# mimic1705.net
KiCad netlist of a schematic drawn in EAGLE
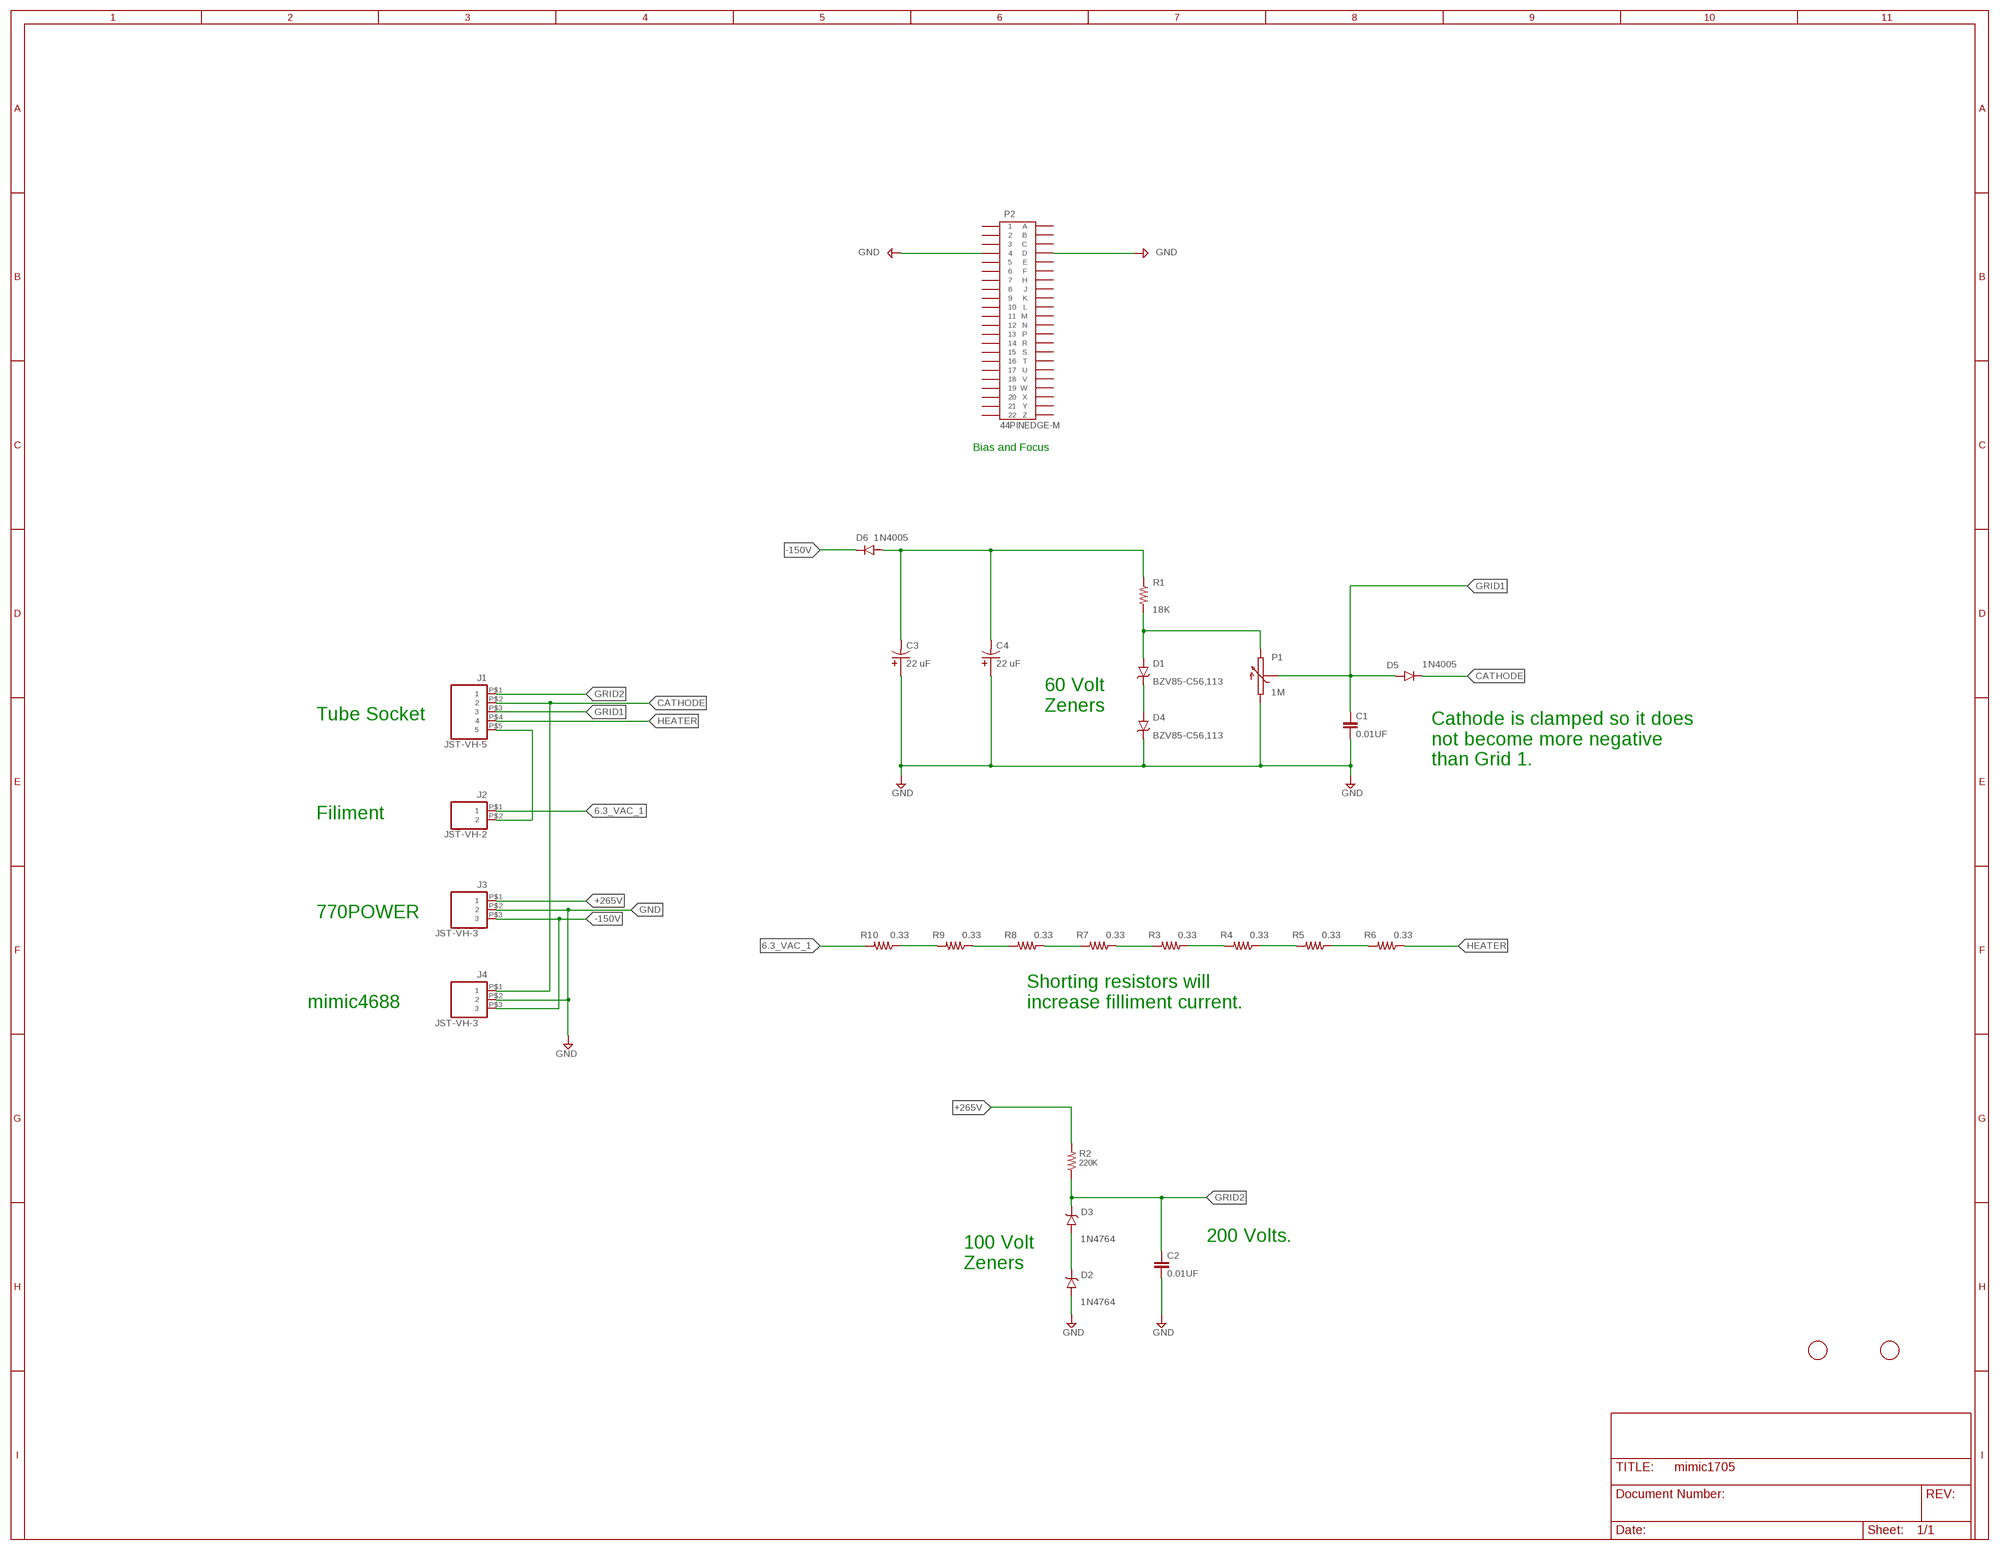
[diagram p0: schematic, sheet 1]

(export (version "E")
  (design (tool "Eeschema 10.0.6"))
  (components
    (comp (ref "C1")
      (value "0.01UF")
      (footprint "eagle-import:5MM_TH")
      (libsource (lib "eagle-import") (part "CAP_5MM"))
    )
    (comp (ref "C2")
      (value "0.01UF")
      (footprint "eagle-import:5MM_TH")
      (libsource (lib "eagle-import") (part "CAP_5MM"))
    )
    (comp (ref "C3")
      (value "22 uF")
      (footprint "eagle-import:AXIAL10X26")
      (libsource (lib "eagle-import") (part "CAP100UF200V"))
    )
    (comp (ref "C4")
      (value "22 uF")
      (footprint "eagle-import:AXIAL10X26")
      (libsource (lib "eagle-import") (part "CAP100UF200V"))
    )
    (comp (ref "D1")
      (value "BZV85-C56,113")
      (footprint "eagle-import:DO-41-10")
      (libsource (lib "eagle-import") (part "BZV85-C56,113"))
    )
    (comp (ref "D2")
      (value "1N4764")
      (footprint "eagle-import:DO-41-10")
      (libsource (lib "eagle-import") (part "1N4764A"))
    )
    (comp (ref "D3")
      (value "1N4764")
      (footprint "eagle-import:DO-41-10")
      (libsource (lib "eagle-import") (part "1N4764A"))
    )
    (comp (ref "D4")
      (value "BZV85-C56,113")
      (footprint "eagle-import:DO-41-10")
      (libsource (lib "eagle-import") (part "BZV85-C56,113"))
    )
    (comp (ref "D5")
      (value "1N4005")
      (footprint "eagle-import:DO-41-10")
      (libsource (lib "eagle-import") (part "1N400X"))
    )
    (comp (ref "D6")
      (value "1N4005")
      (footprint "eagle-import:DO-41-10")
      (libsource (lib "eagle-import") (part "1N400X"))
    )
    (comp (ref "J1")
      (value "JST-VH-5")
      (footprint "eagle-import:VHR-5N")
      (libsource (lib "eagle-import") (part "JST-VH-5"))
    )
    (comp (ref "J2")
      (value "JST-VH-2")
      (footprint "eagle-import:VHR-2N")
      (libsource (lib "eagle-import") (part "JST-VH-2"))
    )
    (comp (ref "J3")
      (value "JST-VH-3")
      (footprint "eagle-import:VHR-3N")
      (libsource (lib "eagle-import") (part "JST-VH-3"))
    )
    (comp (ref "J4")
      (value "JST-VH-3")
      (footprint "eagle-import:VHR-3N")
      (libsource (lib "eagle-import") (part "JST-VH-3"))
    )
    (comp (ref "P1")
      (value "1M")
      (footprint "eagle-import:3006P")
      (libsource (lib "eagle-import") (part "POT-3006P"))
    )
    (comp (ref "P2")
      (value "44PINEDGE-M")
      (footprint "eagle-import:44PINEDGE")
      (libsource (lib "eagle-import") (part "44PINEDGE-M"))
    )
    (comp (ref "R1")
      (value "18K")
      (footprint "eagle-import:0207_10")
      (libsource (lib "eagle-import") (part "RES-V"))
    )
    (comp (ref "R2")
      (value "220K")
      (footprint "eagle-import:0207_10")
      (libsource (lib "eagle-import") (part "RES-V"))
    )
    (comp (ref "R3")
      (value "0.33")
      (footprint "eagle-import:0309_12")
      (libsource (lib "eagle-import") (part "R-1/2WATT"))
    )
    (comp (ref "R4")
      (value "0.33")
      (footprint "eagle-import:0309_12")
      (libsource (lib "eagle-import") (part "R-1/2WATT"))
    )
    (comp (ref "R5")
      (value "0.33")
      (footprint "eagle-import:0309_12")
      (libsource (lib "eagle-import") (part "R-1/2WATT"))
    )
    (comp (ref "R6")
      (value "0.33")
      (footprint "eagle-import:0309_12")
      (libsource (lib "eagle-import") (part "R-1/2WATT"))
    )
    (comp (ref "R7")
      (value "0.33")
      (footprint "eagle-import:0309_12")
      (libsource (lib "eagle-import") (part "R-1/2WATT"))
    )
    (comp (ref "R8")
      (value "0.33")
      (footprint "eagle-import:0309_12")
      (libsource (lib "eagle-import") (part "R-1/2WATT"))
    )
    (comp (ref "R9")
      (value "0.33")
      (footprint "eagle-import:0309_12")
      (libsource (lib "eagle-import") (part "R-1/2WATT"))
    )
    (comp (ref "R10")
      (value "0.33")
      (footprint "eagle-import:0309_12")
      (libsource (lib "eagle-import") (part "R-1/2WATT"))
    )
    (comp (ref "U$1")
      (value "FIDUCIAL")
      (footprint "eagle-import:FIDUCIAL_1MM")
      (libsource (lib "eagle-import") (part "FIDUCIAL"))
    )
    (comp (ref "U$2")
      (value "FIDUCIAL")
      (footprint "eagle-import:FIDUCIAL_1MM")
      (libsource (lib "eagle-import") (part "FIDUCIAL"))
    )
  )
  (nets
    (net (code "1") (name "+265V") (class "Default")
      (node (ref "J3") (pin "P$1") (pinfunction "1_P$1") (pintype "bidirectional"))
      (node (ref "R2") (pin "2") (pinfunction "P$2_2") (pintype "passive"))
    )
    (net (code "2") (name "-150V") (class "Default")
      (node (ref "D6") (pin "C") (pinfunction "C_C") (pintype "passive"))
      (node (ref "J3") (pin "P$3") (pinfunction "3_P$3") (pintype "bidirectional"))
      (node (ref "J4") (pin "P$3") (pinfunction "3_P$3") (pintype "bidirectional"))
    )
    (net (code "3") (name "6.3_VAC_1") (class "Default")
      (node (ref "J2") (pin "P$1") (pinfunction "1_P$1") (pintype "bidirectional"))
      (node (ref "R10") (pin "2") (pinfunction "P$2_2") (pintype "passive"))
    )
    (net (code "4") (name "CATHODE") (class "Default")
      (node (ref "D5") (pin "C") (pinfunction "C_C") (pintype "passive"))
      (node (ref "J1") (pin "P$2") (pinfunction "2_P$2") (pintype "bidirectional"))
      (node (ref "J4") (pin "P$1") (pinfunction "1_P$1") (pintype "bidirectional"))
    )
    (net (code "5") (name "GND") (class "Default")
      (node (ref "C1") (pin "2") (pinfunction "2_2") (pintype "passive"))
      (node (ref "C2") (pin "2") (pinfunction "2_2") (pintype "passive"))
      (node (ref "C3") (pin "P$1") (pinfunction "1_P$1") (pintype "passive"))
      (node (ref "C4") (pin "P$1") (pinfunction "1_P$1") (pintype "passive"))
      (node (ref "D2") (pin "A") (pinfunction "A_A") (pintype "passive"))
      (node (ref "D4") (pin "C") (pinfunction "C_C") (pintype "passive"))
      (node (ref "J3") (pin "P$2") (pinfunction "2_P$2") (pintype "bidirectional"))
      (node (ref "J4") (pin "P$2") (pinfunction "2_P$2") (pintype "bidirectional"))
      (node (ref "P1") (pin "1") (pinfunction "1_1") (pintype "passive"))
      (node (ref "P2") (pin "4") (pinfunction "4_4") (pintype "passive"))
      (node (ref "P2") (pin "D") (pinfunction "D_D") (pintype "passive"))
    )
    (net (code "6") (name "GRID1") (class "Default")
      (node (ref "C1") (pin "1") (pinfunction "1_1") (pintype "passive"))
      (node (ref "D5") (pin "A") (pinfunction "A_A") (pintype "passive"))
      (node (ref "J1") (pin "P$3") (pinfunction "3_P$3") (pintype "bidirectional"))
      (node (ref "P1") (pin "2") (pinfunction "2_2") (pintype "passive"))
    )
    (net (code "7") (name "GRID2") (class "Default")
      (node (ref "C2") (pin "1") (pinfunction "1_1") (pintype "passive"))
      (node (ref "D3") (pin "C") (pinfunction "C_C") (pintype "passive"))
      (node (ref "J1") (pin "P$1") (pinfunction "1_P$1") (pintype "bidirectional"))
      (node (ref "R2") (pin "1") (pinfunction "P$1_1") (pintype "passive"))
    )
    (net (code "8") (name "HEATER") (class "Default")
      (node (ref "J1") (pin "P$4") (pinfunction "4_P$4") (pintype "bidirectional"))
      (node (ref "R6") (pin "1") (pinfunction "P$1_1") (pintype "passive"))
    )
    (net (code "9") (name "Net-(C3-2)") (class "Default")
      (node (ref "C3") (pin "P$2") (pinfunction "2_P$2") (pintype "passive"))
      (node (ref "C4") (pin "P$2") (pinfunction "2_P$2") (pintype "passive"))
      (node (ref "D6") (pin "A") (pinfunction "A_A") (pintype "passive"))
      (node (ref "R1") (pin "1") (pinfunction "P$1_1") (pintype "passive"))
    )
    (net (code "10") (name "Net-(D1-PadC)") (class "Default")
      (node (ref "D1") (pin "C") (pinfunction "C_C") (pintype "passive"))
      (node (ref "D4") (pin "A") (pinfunction "A_A") (pintype "passive"))
    )
    (net (code "11") (name "Net-(D2-PadC)") (class "Default")
      (node (ref "D2") (pin "C") (pinfunction "C_C") (pintype "passive"))
      (node (ref "D3") (pin "A") (pinfunction "A_A") (pintype "passive"))
    )
    (net (code "12") (name "Net-(J1-5)") (class "Default")
      (node (ref "J1") (pin "P$5") (pinfunction "5_P$5") (pintype "bidirectional"))
      (node (ref "J2") (pin "P$2") (pinfunction "2_P$2") (pintype "bidirectional"))
    )
    (net (code "13") (name "Net-(R1-P$2)") (class "Default")
      (node (ref "D1") (pin "A") (pinfunction "A_A") (pintype "passive"))
      (node (ref "P1") (pin "3") (pinfunction "3_3") (pintype "passive"))
      (node (ref "R1") (pin "2") (pinfunction "P$2_2") (pintype "passive"))
    )
    (net (code "14") (name "Net-(R3-P$1)") (class "Default")
      (node (ref "R3") (pin "1") (pinfunction "P$1_1") (pintype "passive"))
      (node (ref "R4") (pin "2") (pinfunction "P$2_2") (pintype "passive"))
    )
    (net (code "15") (name "Net-(R3-P$2)") (class "Default")
      (node (ref "R3") (pin "2") (pinfunction "P$2_2") (pintype "passive"))
      (node (ref "R7") (pin "1") (pinfunction "P$1_1") (pintype "passive"))
    )
    (net (code "16") (name "Net-(R4-P$1)") (class "Default")
      (node (ref "R4") (pin "1") (pinfunction "P$1_1") (pintype "passive"))
      (node (ref "R5") (pin "2") (pinfunction "P$2_2") (pintype "passive"))
    )
    (net (code "17") (name "Net-(R5-P$1)") (class "Default")
      (node (ref "R5") (pin "1") (pinfunction "P$1_1") (pintype "passive"))
      (node (ref "R6") (pin "2") (pinfunction "P$2_2") (pintype "passive"))
    )
    (net (code "18") (name "Net-(R7-P$2)") (class "Default")
      (node (ref "R7") (pin "2") (pinfunction "P$2_2") (pintype "passive"))
      (node (ref "R8") (pin "1") (pinfunction "P$1_1") (pintype "passive"))
    )
    (net (code "19") (name "Net-(R8-P$2)") (class "Default")
      (node (ref "R8") (pin "2") (pinfunction "P$2_2") (pintype "passive"))
      (node (ref "R9") (pin "1") (pinfunction "P$1_1") (pintype "passive"))
    )
    (net (code "20") (name "Net-(R10-P$1)") (class "Default")
      (node (ref "R10") (pin "1") (pinfunction "P$1_1") (pintype "passive"))
      (node (ref "R9") (pin "2") (pinfunction "P$2_2") (pintype "passive"))
    )
    (net (code "21") (name "unconnected-(P2-Pad1)") (class "Default")
      (node (ref "P2") (pin "1") (pinfunction "1_1") (pintype "passive"))
    )
    (net (code "22") (name "unconnected-(P2-Pad2)") (class "Default")
      (node (ref "P2") (pin "2") (pinfunction "2_2") (pintype "passive"))
    )
    (net (code "23") (name "unconnected-(P2-Pad3)") (class "Default")
      (node (ref "P2") (pin "3") (pinfunction "3_3") (pintype "passive"))
    )
    (net (code "24") (name "unconnected-(P2-Pad5)") (class "Default")
      (node (ref "P2") (pin "5") (pinfunction "5_5") (pintype "passive"))
    )
    (net (code "25") (name "unconnected-(P2-Pad6)") (class "Default")
      (node (ref "P2") (pin "6") (pinfunction "6_6") (pintype "passive"))
    )
    (net (code "26") (name "unconnected-(P2-Pad7)") (class "Default")
      (node (ref "P2") (pin "7") (pinfunction "7_7") (pintype "passive"))
    )
    (net (code "27") (name "unconnected-(P2-Pad8)") (class "Default")
      (node (ref "P2") (pin "8") (pinfunction "8_8") (pintype "passive"))
    )
    (net (code "28") (name "unconnected-(P2-Pad9)") (class "Default")
      (node (ref "P2") (pin "9") (pinfunction "9_9") (pintype "passive"))
    )
    (net (code "29") (name "unconnected-(P2-Pad10)") (class "Default")
      (node (ref "P2") (pin "10") (pinfunction "10_10") (pintype "passive"))
    )
    (net (code "30") (name "unconnected-(P2-Pad11)") (class "Default")
      (node (ref "P2") (pin "11") (pinfunction "11_11") (pintype "passive"))
    )
    (net (code "31") (name "unconnected-(P2-Pad12)") (class "Default")
      (node (ref "P2") (pin "12") (pinfunction "12_12") (pintype "passive"))
    )
    (net (code "32") (name "unconnected-(P2-Pad13)") (class "Default")
      (node (ref "P2") (pin "13") (pinfunction "13_13") (pintype "passive"))
    )
    (net (code "33") (name "unconnected-(P2-Pad14)") (class "Default")
      (node (ref "P2") (pin "14") (pinfunction "14_14") (pintype "passive"))
    )
    (net (code "34") (name "unconnected-(P2-Pad15)") (class "Default")
      (node (ref "P2") (pin "15") (pinfunction "15_15") (pintype "passive"))
    )
    (net (code "35") (name "unconnected-(P2-Pad16)") (class "Default")
      (node (ref "P2") (pin "16") (pinfunction "16_16") (pintype "passive"))
    )
    (net (code "36") (name "unconnected-(P2-Pad17)") (class "Default")
      (node (ref "P2") (pin "17") (pinfunction "17_17") (pintype "passive"))
    )
    (net (code "37") (name "unconnected-(P2-Pad18)") (class "Default")
      (node (ref "P2") (pin "18") (pinfunction "18_18") (pintype "passive"))
    )
    (net (code "38") (name "unconnected-(P2-Pad19)") (class "Default")
      (node (ref "P2") (pin "19") (pinfunction "19_19") (pintype "passive"))
    )
    (net (code "39") (name "unconnected-(P2-Pad20)") (class "Default")
      (node (ref "P2") (pin "20") (pinfunction "20_20") (pintype "passive"))
    )
    (net (code "40") (name "unconnected-(P2-Pad21)") (class "Default")
      (node (ref "P2") (pin "21") (pinfunction "21_21") (pintype "passive"))
    )
    (net (code "41") (name "unconnected-(P2-Pad22)") (class "Default")
      (node (ref "P2") (pin "22") (pinfunction "22_22") (pintype "passive"))
    )
    (net (code "42") (name "unconnected-(P2-PadA)") (class "Default")
      (node (ref "P2") (pin "A") (pinfunction "A_A") (pintype "passive"))
    )
    (net (code "43") (name "unconnected-(P2-PadB)") (class "Default")
      (node (ref "P2") (pin "B") (pinfunction "B_B") (pintype "passive"))
    )
    (net (code "44") (name "unconnected-(P2-PadC)") (class "Default")
      (node (ref "P2") (pin "C") (pinfunction "C_C") (pintype "passive"))
    )
    (net (code "45") (name "unconnected-(P2-PadE)") (class "Default")
      (node (ref "P2") (pin "E") (pinfunction "E_E") (pintype "passive"))
    )
    (net (code "46") (name "unconnected-(P2-PadF)") (class "Default")
      (node (ref "P2") (pin "F") (pinfunction "F_F") (pintype "passive"))
    )
    (net (code "47") (name "unconnected-(P2-PadH)") (class "Default")
      (node (ref "P2") (pin "H") (pinfunction "H_H") (pintype "passive"))
    )
    (net (code "48") (name "unconnected-(P2-PadJ)") (class "Default")
      (node (ref "P2") (pin "J") (pinfunction "J_J") (pintype "passive"))
    )
    (net (code "49") (name "unconnected-(P2-PadK)") (class "Default")
      (node (ref "P2") (pin "K") (pinfunction "K_K") (pintype "passive"))
    )
    (net (code "50") (name "unconnected-(P2-PadL)") (class "Default")
      (node (ref "P2") (pin "L") (pinfunction "L_L") (pintype "passive"))
    )
    (net (code "51") (name "unconnected-(P2-PadM)") (class "Default")
      (node (ref "P2") (pin "M") (pinfunction "M_M") (pintype "passive"))
    )
    (net (code "52") (name "unconnected-(P2-PadN)") (class "Default")
      (node (ref "P2") (pin "N") (pinfunction "N_N") (pintype "passive"))
    )
    (net (code "53") (name "unconnected-(P2-PadP)") (class "Default")
      (node (ref "P2") (pin "P") (pinfunction "P_P") (pintype "passive"))
    )
    (net (code "54") (name "unconnected-(P2-PadR)") (class "Default")
      (node (ref "P2") (pin "R") (pinfunction "R_R") (pintype "passive"))
    )
    (net (code "55") (name "unconnected-(P2-PadS)") (class "Default")
      (node (ref "P2") (pin "S") (pinfunction "S_S") (pintype "passive"))
    )
    (net (code "56") (name "unconnected-(P2-PadT)") (class "Default")
      (node (ref "P2") (pin "T") (pinfunction "T_T") (pintype "passive"))
    )
    (net (code "57") (name "unconnected-(P2-PadU)") (class "Default")
      (node (ref "P2") (pin "U") (pinfunction "U_U") (pintype "passive"))
    )
    (net (code "58") (name "unconnected-(P2-PadV)") (class "Default")
      (node (ref "P2") (pin "V") (pinfunction "V_V") (pintype "passive"))
    )
    (net (code "59") (name "unconnected-(P2-PadW)") (class "Default")
      (node (ref "P2") (pin "W") (pinfunction "W_W") (pintype "passive"))
    )
    (net (code "60") (name "unconnected-(P2-PadX)") (class "Default")
      (node (ref "P2") (pin "X") (pinfunction "X_X") (pintype "passive"))
    )
    (net (code "61") (name "unconnected-(P2-PadY)") (class "Default")
      (node (ref "P2") (pin "Y") (pinfunction "Y_Y") (pintype "passive"))
    )
    (net (code "62") (name "unconnected-(P2-PadZ)") (class "Default")
      (node (ref "P2") (pin "Z") (pinfunction "Z_Z") (pintype "passive"))
    )
  )
)
